# SparkFun_Si4703_Eval_Board.net
KiCad netlist of a schematic drawn in EAGLE
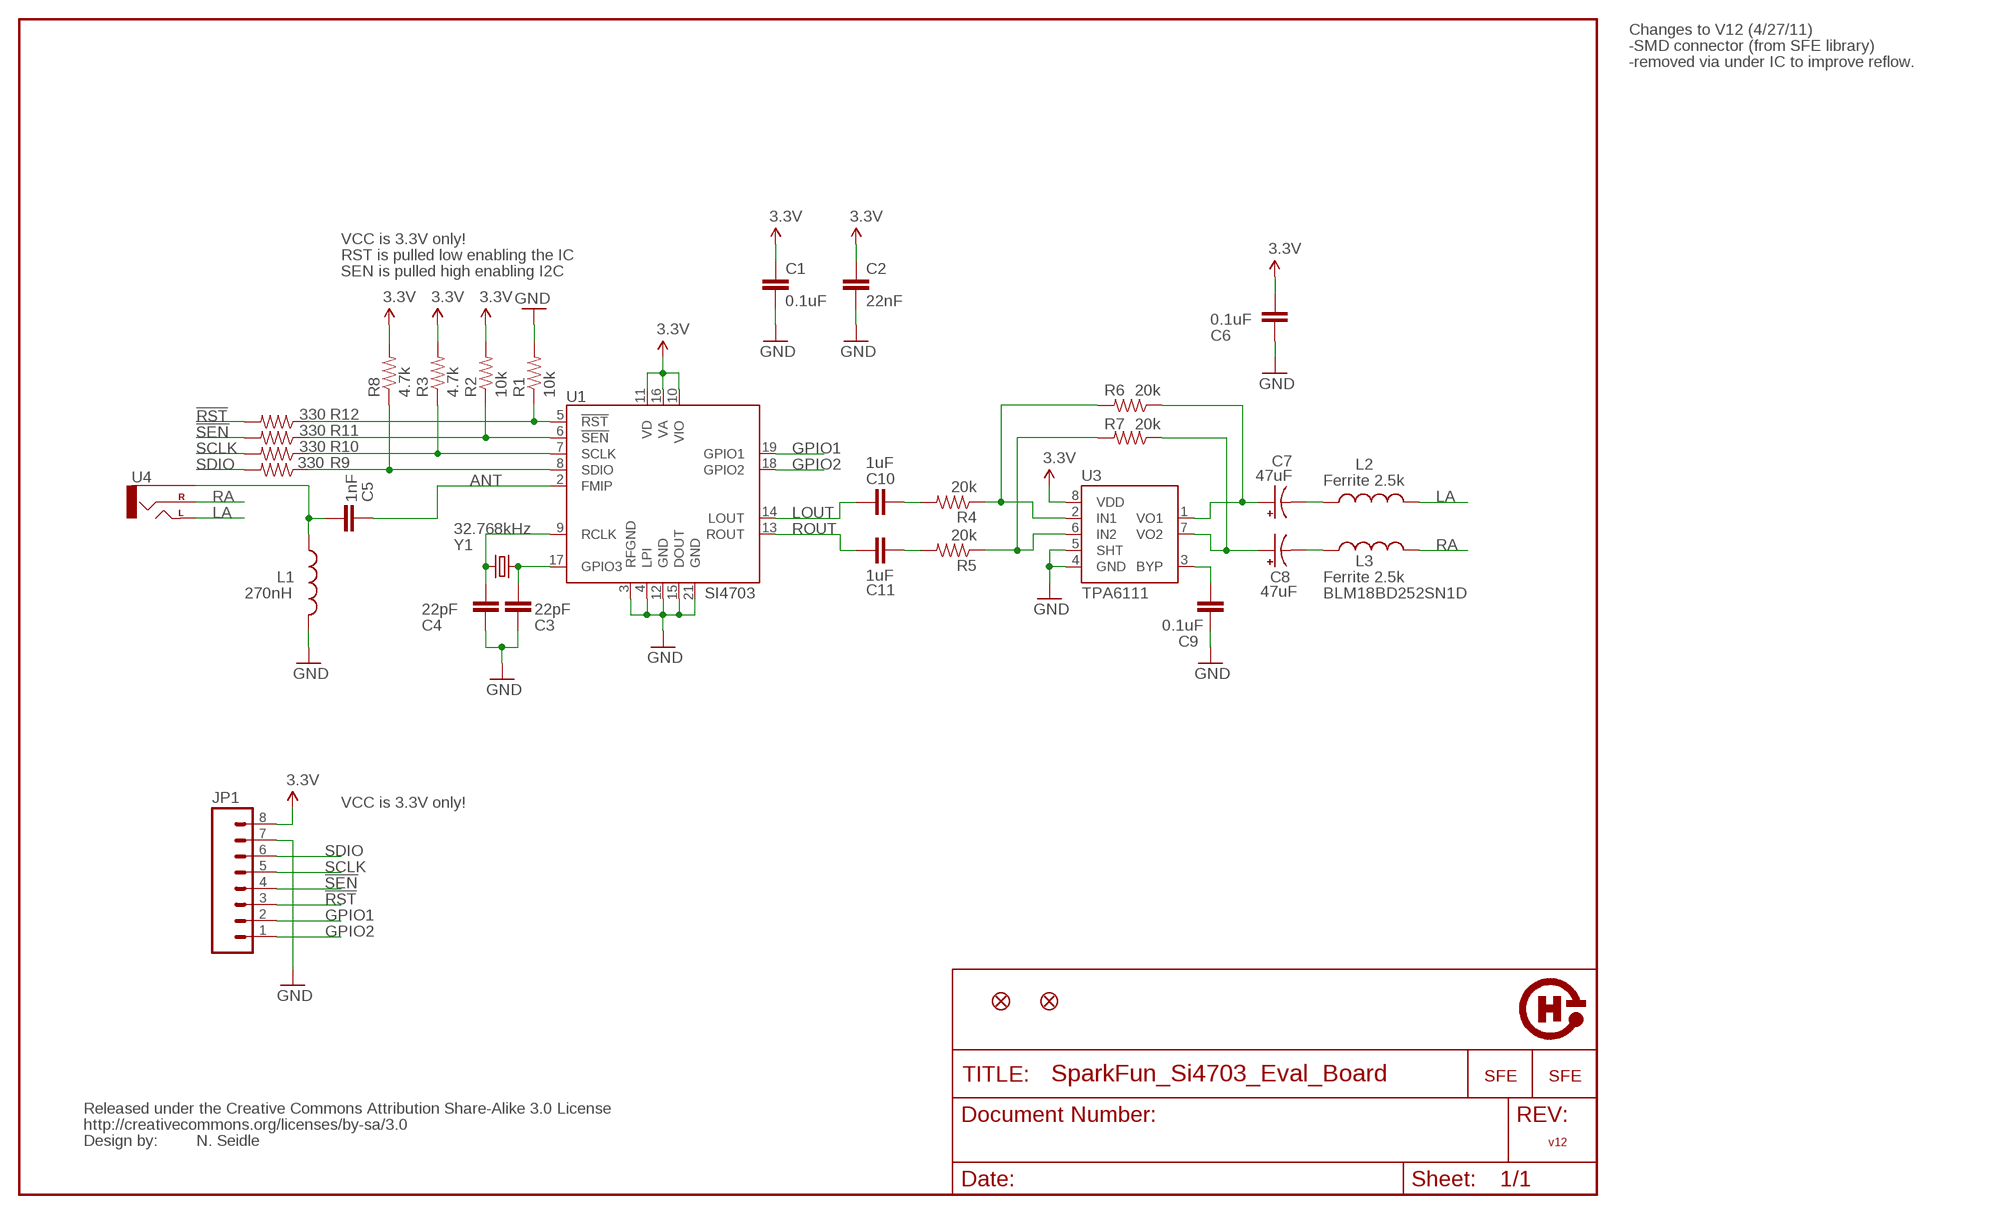
[diagram p0: schematic, sheet 1]

(export (version "E")
  (design (tool "Eeschema 10.0.6"))
  (components
    (comp (ref "C1")
      (value "0.1uF")
      (footprint "eagle-import:0402-CAP")
      (libsource (lib "eagle-import") (part "CAP0402-CAP"))
    )
    (comp (ref "C2")
      (value "22nF")
      (footprint "eagle-import:0402-CAP")
      (libsource (lib "eagle-import") (part "CAP0402-CAP"))
    )
    (comp (ref "C3")
      (value "22pF")
      (footprint "eagle-import:0402-CAP")
      (libsource (lib "eagle-import") (part "CAP0402-CAP"))
    )
    (comp (ref "C4")
      (value "22pF")
      (footprint "eagle-import:0402-CAP")
      (libsource (lib "eagle-import") (part "CAP0402-CAP"))
    )
    (comp (ref "C5")
      (value "1nF")
      (footprint "eagle-import:0402-CAP")
      (libsource (lib "eagle-import") (part "CAP0402-CAP"))
    )
    (comp (ref "C6")
      (value "0.1uF")
      (footprint "eagle-import:0402-CAP")
      (libsource (lib "eagle-import") (part "CAP0402-CAP"))
    )
    (comp (ref "C7")
      (value "47uF")
      (footprint "eagle-import:EIA3528")
      (libsource (lib "eagle-import") (part "CAP_POL3528"))
    )
    (comp (ref "C8")
      (value "47uF")
      (footprint "eagle-import:EIA3528")
      (libsource (lib "eagle-import") (part "CAP_POL3528"))
    )
    (comp (ref "C9")
      (value "0.1uF")
      (footprint "eagle-import:0402-CAP")
      (libsource (lib "eagle-import") (part "CAP0402-CAP"))
    )
    (comp (ref "C10")
      (value "1uF")
      (footprint "eagle-import:0402-CAP")
      (libsource (lib "eagle-import") (part "CAP0402-CAP"))
    )
    (comp (ref "C11")
      (value "1uF")
      (footprint "eagle-import:0402-CAP")
      (libsource (lib "eagle-import") (part "CAP0402-CAP"))
    )
    (comp (ref "JP1")
      (value "M08")
      (footprint "eagle-import:1X08")
      (libsource (lib "eagle-import") (part "M08"))
    )
    (comp (ref "JP2")
      (value "LOGO-SFENEW")
      (footprint "eagle-import:SFE-NEW-WEBLOGO")
      (libsource (lib "eagle-import") (part "LOGO-SFENEW"))
    )
    (comp (ref "JP3")
      (value "LOGO-SFESK")
      (footprint "eagle-import:SFE-LOGO-FLAME")
      (libsource (lib "eagle-import") (part "LOGO-SFESK"))
    )
    (comp (ref "JP4")
      (value "FIDUCIAL1X2")
      (footprint "eagle-import:FIDUCIAL-1X2")
      (libsource (lib "eagle-import") (part "FIDUCIAL1X2"))
    )
    (comp (ref "JP5")
      (value "FIDUCIAL1X2")
      (footprint "eagle-import:FIDUCIAL-1X2")
      (libsource (lib "eagle-import") (part "FIDUCIAL1X2"))
    )
    (comp (ref "L1")
      (value "270nH")
      (footprint "eagle-import:C0402")
      (libsource (lib "eagle-import") (part "INDUCTOR0402"))
    )
    (comp (ref "L2")
      (value "Ferrite 2.5k")
      (footprint "eagle-import:C0402")
      (libsource (lib "eagle-import") (part "INDUCTOR0402"))
    )
    (comp (ref "L3")
      (value "Ferrite 2.5k")
      (footprint "eagle-import:C0402")
      (libsource (lib "eagle-import") (part "INDUCTOR0402"))
    )
    (comp (ref "R1")
      (value "10k")
      (footprint "eagle-import:0402-RES")
      (libsource (lib "eagle-import") (part "RESISTOR0402-RES"))
    )
    (comp (ref "R2")
      (value "10k")
      (footprint "eagle-import:0402-RES")
      (libsource (lib "eagle-import") (part "RESISTOR0402-RES"))
    )
    (comp (ref "R3")
      (value "4.7k")
      (footprint "eagle-import:0402-RES")
      (libsource (lib "eagle-import") (part "RESISTOR0402-RES"))
    )
    (comp (ref "R4")
      (value "20k")
      (footprint "eagle-import:0402-RES")
      (libsource (lib "eagle-import") (part "RESISTOR0402-RES"))
    )
    (comp (ref "R5")
      (value "20k")
      (footprint "eagle-import:0402-RES")
      (libsource (lib "eagle-import") (part "RESISTOR0402-RES"))
    )
    (comp (ref "R6")
      (value "20k")
      (footprint "eagle-import:0402-RES")
      (libsource (lib "eagle-import") (part "RESISTOR0402-RES"))
    )
    (comp (ref "R7")
      (value "20k")
      (footprint "eagle-import:0402-RES")
      (libsource (lib "eagle-import") (part "RESISTOR0402-RES"))
    )
    (comp (ref "R8")
      (value "4.7k")
      (footprint "eagle-import:0402-RES")
      (libsource (lib "eagle-import") (part "RESISTOR0402-RES"))
    )
    (comp (ref "R9")
      (value "330")
      (footprint "eagle-import:0402-RES")
      (libsource (lib "eagle-import") (part "RESISTOR0402-RES"))
    )
    (comp (ref "R10")
      (value "330")
      (footprint "eagle-import:0402-RES")
      (libsource (lib "eagle-import") (part "RESISTOR0402-RES"))
    )
    (comp (ref "R11")
      (value "330")
      (footprint "eagle-import:0402-RES")
      (libsource (lib "eagle-import") (part "RESISTOR0402-RES"))
    )
    (comp (ref "R12")
      (value "330")
      (footprint "eagle-import:0402-RES")
      (libsource (lib "eagle-import") (part "RESISTOR0402-RES"))
    )
    (comp (ref "U$1")
      (value "CREATIVE_COMMONS")
      (footprint "eagle-import:CREATIVE_COMMONS")
      (libsource (lib "eagle-import") (part "CREATIVE_COMMONS"))
    )
    (comp (ref "U$2")
      (value "OSHW-LOGO")
      (footprint "eagle-import:OSHW-LOGO")
      (libsource (lib "eagle-import") (part "OSHW-LOGO"))
    )
    (comp (ref "U1")
      (value "SI4703")
      (footprint "eagle-import:SI470X")
      (libsource (lib "eagle-import") (part "SI470X"))
    )
    (comp (ref "U3")
      (value "TPA6111")
      (footprint "eagle-import:SO08")
      (libsource (lib "eagle-import") (part "TPA6111SMD"))
    )
    (comp (ref "U4")
      (value "AUDIO-JACKSMD2")
      (footprint "eagle-import:AUDIO-JACK-3.5MM-SMD")
      (libsource (lib "eagle-import") (part "AUDIO-JACKSMD2"))
    )
    (comp (ref "Y1")
      (value "32.768kHz")
      (footprint "eagle-import:CRYSTAL-32KHZ-SMD")
      (libsource (lib "eagle-import") (part "CRYSTAL32-SMD"))
    )
  )
  (nets
    (net (code "1") (name "/ANT") (class "Default")
      (node (ref "C5") (pin "1") (pinfunction "1_1") (pintype "passive"))
      (node (ref "U1") (pin "2") (pinfunction "FMIP_2") (pintype "bidirectional"))
    )
    (net (code "2") (name "/GPIO1") (class "Default")
      (node (ref "JP1") (pin "2") (pinfunction "2_2") (pintype "passive"))
      (node (ref "U1") (pin "19") (pinfunction "GPIO1_19") (pintype "bidirectional"))
    )
    (net (code "3") (name "/GPIO2") (class "Default")
      (node (ref "JP1") (pin "1") (pinfunction "1_1") (pintype "passive"))
      (node (ref "U1") (pin "18") (pinfunction "GPIO2_18") (pintype "bidirectional"))
    )
    (net (code "4") (name "/LA") (class "Default")
      (node (ref "L2") (pin "2") (pinfunction "2_2") (pintype "passive"))
      (node (ref "U4") (pin "TIP") (pinfunction "LEFT_TIP") (pintype "bidirectional"))
    )
    (net (code "5") (name "/LOUT") (class "Default")
      (node (ref "C10") (pin "1") (pinfunction "1_1") (pintype "passive"))
      (node (ref "U1") (pin "14") (pinfunction "LOUT_14") (pintype "bidirectional"))
    )
    (net (code "6") (name "/RA") (class "Default")
      (node (ref "L3") (pin "2") (pinfunction "2_2") (pintype "passive"))
      (node (ref "U4") (pin "RING") (pinfunction "RIGHT_RING") (pintype "bidirectional"))
    )
    (net (code "7") (name "/ROUT") (class "Default")
      (node (ref "C11") (pin "1") (pinfunction "1_1") (pintype "passive"))
      (node (ref "U1") (pin "13") (pinfunction "ROUT_13") (pintype "bidirectional"))
    )
    (net (code "8") (name "/SCLK") (class "Default")
      (node (ref "JP1") (pin "5") (pinfunction "5_5") (pintype "passive"))
      (node (ref "R10") (pin "2") (pinfunction "2_2") (pintype "passive"))
    )
    (net (code "9") (name "/SDIO") (class "Default")
      (node (ref "JP1") (pin "6") (pinfunction "6_6") (pintype "passive"))
      (node (ref "R9") (pin "2") (pinfunction "2_2") (pintype "passive"))
    )
    (net (code "10") (name "/~{RST}") (class "Default")
      (node (ref "JP1") (pin "3") (pinfunction "3_3") (pintype "passive"))
      (node (ref "R12") (pin "2") (pinfunction "2_2") (pintype "passive"))
    )
    (net (code "11") (name "/~{SEN}") (class "Default")
      (node (ref "JP1") (pin "4") (pinfunction "4_4") (pintype "passive"))
      (node (ref "R11") (pin "2") (pinfunction "2_2") (pintype "passive"))
    )
    (net (code "12") (name "3.3V") (class "Default")
      (node (ref "C1") (pin "1") (pinfunction "1_1") (pintype "passive"))
      (node (ref "C2") (pin "1") (pinfunction "1_1") (pintype "passive"))
      (node (ref "C6") (pin "2") (pinfunction "2_2") (pintype "passive"))
      (node (ref "JP1") (pin "8") (pinfunction "8_8") (pintype "passive"))
      (node (ref "R2") (pin "2") (pinfunction "2_2") (pintype "passive"))
      (node (ref "R3") (pin "2") (pinfunction "2_2") (pintype "passive"))
      (node (ref "R8") (pin "2") (pinfunction "2_2") (pintype "passive"))
      (node (ref "U1") (pin "10") (pinfunction "VIO_10") (pintype "bidirectional"))
      (node (ref "U1") (pin "11") (pinfunction "VD_11") (pintype "bidirectional"))
      (node (ref "U1") (pin "16") (pinfunction "VA_16") (pintype "bidirectional"))
      (node (ref "U3") (pin "8") (pinfunction "VDD_8") (pintype "bidirectional"))
    )
    (net (code "13") (name "GND") (class "Default")
      (node (ref "C1") (pin "2") (pinfunction "2_2") (pintype "passive"))
      (node (ref "C2") (pin "2") (pinfunction "2_2") (pintype "passive"))
      (node (ref "C3") (pin "1") (pinfunction "1_1") (pintype "passive"))
      (node (ref "C4") (pin "1") (pinfunction "1_1") (pintype "passive"))
      (node (ref "C6") (pin "1") (pinfunction "1_1") (pintype "passive"))
      (node (ref "C9") (pin "2") (pinfunction "2_2") (pintype "passive"))
      (node (ref "JP1") (pin "7") (pinfunction "7_7") (pintype "passive"))
      (node (ref "L1") (pin "2") (pinfunction "2_2") (pintype "passive"))
      (node (ref "R1") (pin "2") (pinfunction "2_2") (pintype "passive"))
      (node (ref "U1") (pin "12") (pinfunction "GND_12") (pintype "bidirectional"))
      (node (ref "U1") (pin "15") (pinfunction "DOUT_15") (pintype "bidirectional"))
      (node (ref "U1") (pin "21") (pinfunction "GND_21") (pintype "bidirectional"))
      (node (ref "U1") (pin "3") (pinfunction "RFGND_3") (pintype "bidirectional"))
      (node (ref "U1") (pin "4") (pinfunction "LPI_4") (pintype "bidirectional"))
      (node (ref "U3") (pin "4") (pinfunction "GND_4") (pintype "bidirectional"))
      (node (ref "U3") (pin "5") (pinfunction "SHT_5") (pintype "bidirectional"))
    )
    (net (code "14") (name "Net-(C5-Pad2)") (class "Default")
      (node (ref "C5") (pin "2") (pinfunction "2_2") (pintype "passive"))
      (node (ref "L1") (pin "1") (pinfunction "1_1") (pintype "passive"))
      (node (ref "U4") (pin "SLEEVE") (pinfunction "SLEEVE_SLEEVE") (pintype "bidirectional"))
    )
    (net (code "15") (name "Net-(C7-+)") (class "Default")
      (node (ref "C7") (pin "A") (pinfunction "+_A") (pintype "passive"))
      (node (ref "R6") (pin "1") (pinfunction "1_1") (pintype "passive"))
      (node (ref "U3") (pin "1") (pinfunction "VO1_1") (pintype "bidirectional"))
    )
    (net (code "16") (name "Net-(C7--)") (class "Default")
      (node (ref "C7") (pin "C") (pinfunction "-_C") (pintype "passive"))
      (node (ref "L2") (pin "1") (pinfunction "1_1") (pintype "passive"))
    )
    (net (code "17") (name "Net-(C8-+)") (class "Default")
      (node (ref "C8") (pin "A") (pinfunction "+_A") (pintype "passive"))
      (node (ref "R7") (pin "1") (pinfunction "1_1") (pintype "passive"))
      (node (ref "U3") (pin "7") (pinfunction "VO2_7") (pintype "bidirectional"))
    )
    (net (code "18") (name "Net-(C8--)") (class "Default")
      (node (ref "C8") (pin "C") (pinfunction "-_C") (pintype "passive"))
      (node (ref "L3") (pin "1") (pinfunction "1_1") (pintype "passive"))
    )
    (net (code "19") (name "Net-(C10-Pad2)") (class "Default")
      (node (ref "C10") (pin "2") (pinfunction "2_2") (pintype "passive"))
      (node (ref "R4") (pin "2") (pinfunction "2_2") (pintype "passive"))
    )
    (net (code "20") (name "Net-(C11-Pad2)") (class "Default")
      (node (ref "C11") (pin "2") (pinfunction "2_2") (pintype "passive"))
      (node (ref "R5") (pin "2") (pinfunction "2_2") (pintype "passive"))
    )
    (net (code "21") (name "Net-(U1-GPIO3)") (class "Default")
      (node (ref "C3") (pin "2") (pinfunction "2_2") (pintype "passive"))
      (node (ref "U1") (pin "17") (pinfunction "GPIO3_17") (pintype "bidirectional"))
      (node (ref "Y1") (pin "X1") (pinfunction "1_X1") (pintype "passive"))
    )
    (net (code "22") (name "Net-(U1-RCLK)") (class "Default")
      (node (ref "C4") (pin "2") (pinfunction "2_2") (pintype "passive"))
      (node (ref "U1") (pin "9") (pinfunction "RCLK_9") (pintype "bidirectional"))
      (node (ref "Y1") (pin "X2") (pinfunction "2_X2") (pintype "passive"))
    )
    (net (code "23") (name "Net-(U1-SCLK)") (class "Default")
      (node (ref "R10") (pin "1") (pinfunction "1_1") (pintype "passive"))
      (node (ref "R3") (pin "1") (pinfunction "1_1") (pintype "passive"))
      (node (ref "U1") (pin "7") (pinfunction "SCLK_7") (pintype "bidirectional"))
    )
    (net (code "24") (name "Net-(U1-SDIO)") (class "Default")
      (node (ref "R8") (pin "1") (pinfunction "1_1") (pintype "passive"))
      (node (ref "R9") (pin "1") (pinfunction "1_1") (pintype "passive"))
      (node (ref "U1") (pin "8") (pinfunction "SDIO_8") (pintype "bidirectional"))
    )
    (net (code "25") (name "Net-(U1-~{RST})") (class "Default")
      (node (ref "R1") (pin "1") (pinfunction "1_1") (pintype "passive"))
      (node (ref "R12") (pin "1") (pinfunction "1_1") (pintype "passive"))
      (node (ref "U1") (pin "5") (pinfunction "~{RST}_5") (pintype "bidirectional"))
    )
    (net (code "26") (name "Net-(U1-~{SEN})") (class "Default")
      (node (ref "R11") (pin "1") (pinfunction "1_1") (pintype "passive"))
      (node (ref "R2") (pin "1") (pinfunction "1_1") (pintype "passive"))
      (node (ref "U1") (pin "6") (pinfunction "~{SEN}_6") (pintype "bidirectional"))
    )
    (net (code "27") (name "Net-(U3-BYP)") (class "Default")
      (node (ref "C9") (pin "1") (pinfunction "1_1") (pintype "passive"))
      (node (ref "U3") (pin "3") (pinfunction "BYP_3") (pintype "bidirectional"))
    )
    (net (code "28") (name "Net-(U3-IN1)") (class "Default")
      (node (ref "R4") (pin "1") (pinfunction "1_1") (pintype "passive"))
      (node (ref "R6") (pin "2") (pinfunction "2_2") (pintype "passive"))
      (node (ref "U3") (pin "2") (pinfunction "IN1_2") (pintype "bidirectional"))
    )
    (net (code "29") (name "Net-(U3-IN2)") (class "Default")
      (node (ref "R5") (pin "1") (pinfunction "1_1") (pintype "passive"))
      (node (ref "R7") (pin "2") (pinfunction "2_2") (pintype "passive"))
      (node (ref "U3") (pin "6") (pinfunction "IN2_6") (pintype "bidirectional"))
    )
  )
)
